# POWER_HALL.net
KiCad netlist of a schematic drawn in Altium Designer
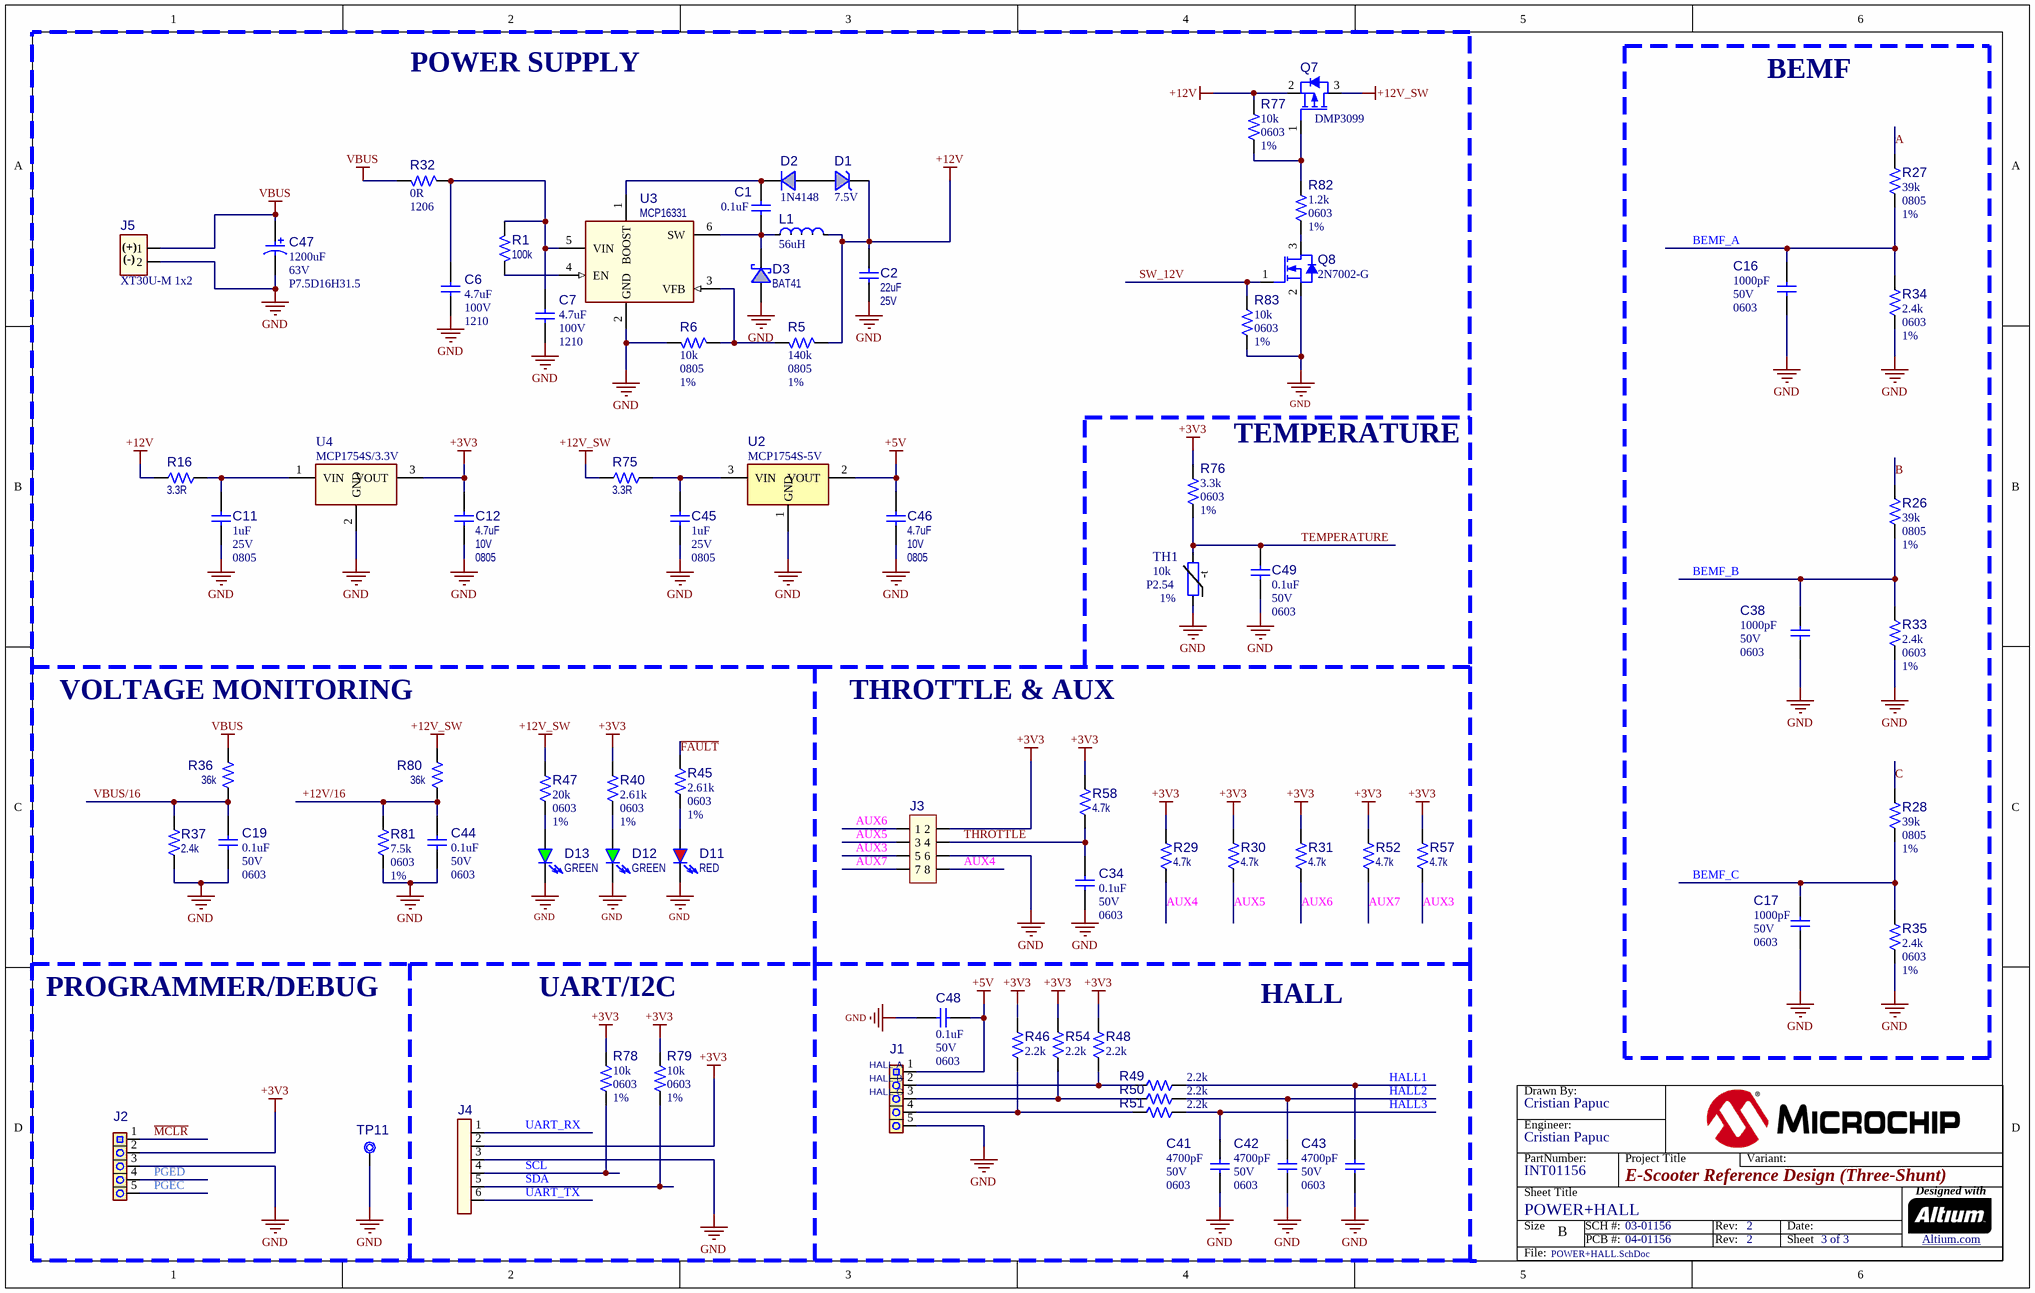
[diagram p0: POWER+HALL.SchDoc]

(export (version "E")
  (design (tool "Eeschema 10.0.6"))
  (components
    (comp (ref "C1")
      (value "0.1uF")
      (footprint "CAP_C_0603")
      (description "Capacitor")
      (fields
        (field (name "VOLTAGE") "50V")
        (field (name "TOLERANCE") "10%")
        (field (name "OWNER") "Sam Charles")
      )
      (libsource (lib "MCHP-CDB") (part "Capacitor NP"))
    )
    (comp (ref "C2")
      (value "22uF")
      (footprint "CAP_C_1206")
      (description "Capacitor")
      (fields
        (field (name "VOLTAGE") "25V")
        (field (name "TOLERANCE") "10%")
        (field (name "Comment") "Capacitor NP")
        (field (name "OWNER") "Jose Garcia")
      )
      (libsource (lib "") (part "Capacitor NP_1"))
    )
    (comp (ref "C6")
      (value "4.7uF")
      (footprint "CAP_C_1210")
      (description "Capacitor")
      (fields
        (field (name "VOLTAGE") "100V")
        (field (name "PACKAGE") "1210")
        (field (name "TOLERANCE") "10%")
        (field (name "Comment") "Capacitor NP")
        (field (name "OWNER") "Cristian Papuc")
      )
      (libsource (lib "MCHP-CDB") (part "Capacitor NP"))
    )
    (comp (ref "C7")
      (value "4.7uF")
      (footprint "CAP_C_1210")
      (description "Capacitor")
      (fields
        (field (name "VOLTAGE") "100V")
        (field (name "PACKAGE") "1210")
        (field (name "TOLERANCE") "10%")
        (field (name "Comment") "Capacitor NP")
        (field (name "OWNER") "Cristian Papuc")
      )
      (libsource (lib "MCHP-CDB") (part "Capacitor NP"))
    )
    (comp (ref "C11")
      (value "1uF")
      (footprint "CAP_C_0805")
      (description "Capacitor")
      (fields
        (field (name "VOLTAGE") "25V")
        (field (name "PACKAGE") "0805")
        (field (name "TOLERANCE") "10%")
        (field (name "Comment") "Capacitor NP")
        (field (name "OWNER") "Tad Ahlvers")
      )
      (libsource (lib "MCHP-CDB") (part "Capacitor NP"))
    )
    (comp (ref "C12")
      (value "4.7uF")
      (footprint "CAP_C_0805")
      (description "Capacitor")
      (fields
        (field (name "VOLTAGE") "10V")
        (field (name "PACKAGE") "0805")
        (field (name "TOLERANCE") "20%")
        (field (name "Comment") "Capacitor NP")
        (field (name "OWNER") "Mark Loper")
      )
      (libsource (lib "") (part "Capacitor NP_1"))
    )
    (comp (ref "C16")
      (value "1000pF")
      (footprint "CAP_C_0603")
      (description "Capacitor")
      (fields
        (field (name "VOLTAGE") "50V")
        (field (name "PACKAGE") "0603")
        (field (name "TOLERANCE") "10%")
        (field (name "Comment") "Capacitor NP")
      )
      (libsource (lib "") (part "Capacitor NP_1"))
    )
    (comp (ref "C17")
      (value "1000pF")
      (footprint "CAP_C_0603")
      (description "Capacitor")
      (fields
        (field (name "VOLTAGE") "50V")
        (field (name "PACKAGE") "0603")
        (field (name "TOLERANCE") "10%")
        (field (name "Comment") "Capacitor NP")
      )
      (libsource (lib "") (part "Capacitor NP_1"))
    )
    (comp (ref "C19")
      (value "0.1uF")
      (footprint "CAP_C_0603")
      (description "Capacitor")
      (fields
        (field (name "VOLTAGE") "50V")
        (field (name "PACKAGE") "0603")
        (field (name "TOLERANCE") "10%")
        (field (name "Comment") "Capacitor NP")
        (field (name "OWNER") "Sam Charles")
      )
      (libsource (lib "MCHP-CDB") (part "Capacitor NP"))
    )
    (comp (ref "C34")
      (value "0.1uF")
      (footprint "CAP_C_0603")
      (description "Capacitor")
      (fields
        (field (name "VOLTAGE") "50V")
        (field (name "PACKAGE") "0603")
        (field (name "TOLERANCE") "10%")
        (field (name "Comment") "Capacitor NP")
        (field (name "OWNER") "Sam Charles")
      )
      (libsource (lib "MCHP-CDB") (part "Capacitor NP"))
    )
    (comp (ref "C38")
      (value "1000pF")
      (footprint "CAP_C_0603")
      (description "Capacitor")
      (fields
        (field (name "VOLTAGE") "50V")
        (field (name "PACKAGE") "0603")
        (field (name "TOLERANCE") "10%")
        (field (name "Comment") "Capacitor NP")
      )
      (libsource (lib "") (part "Capacitor NP_1"))
    )
    (comp (ref "C41")
      (value "4700pF")
      (footprint "CAP_C_0603")
      (fields
        (field (name "VOLTAGE") "50V")
        (field (name "PACKAGE") "0603")
        (field (name "TOLERANCE") "10%")
        (field (name "Comment") "Capacitor NP")
        (field (name "OWNER") "Miahi T(M91442)")
      )
      (libsource (lib "MCHP-CDB") (part "Capacitor NP"))
    )
    (comp (ref "C42")
      (value "4700pF")
      (footprint "CAP_C_0603")
      (fields
        (field (name "VOLTAGE") "50V")
        (field (name "PACKAGE") "0603")
        (field (name "TOLERANCE") "10%")
        (field (name "Comment") "Capacitor NP")
        (field (name "OWNER") "Miahi T(M91442)")
      )
      (libsource (lib "MCHP-CDB") (part "Capacitor NP"))
    )
    (comp (ref "C43")
      (value "4700pF")
      (footprint "CAP_C_0603")
      (fields
        (field (name "VOLTAGE") "50V")
        (field (name "PACKAGE") "0603")
        (field (name "TOLERANCE") "10%")
        (field (name "Comment") "Capacitor NP")
        (field (name "OWNER") "Miahi T(M91442)")
      )
      (libsource (lib "MCHP-CDB") (part "Capacitor NP"))
    )
    (comp (ref "C44")
      (value "0.1uF")
      (footprint "CAP_C_0603")
      (description "Capacitor")
      (fields
        (field (name "VOLTAGE") "50V")
        (field (name "PACKAGE") "0603")
        (field (name "TOLERANCE") "10%")
        (field (name "Comment") "Capacitor NP")
        (field (name "OWNER") "Sam Charles")
      )
      (libsource (lib "MCHP-CDB") (part "Capacitor NP"))
    )
    (comp (ref "C45")
      (value "1uF")
      (footprint "CAP_C_0805")
      (description "Capacitor")
      (fields
        (field (name "VOLTAGE") "25V")
        (field (name "PACKAGE") "0805")
        (field (name "TOLERANCE") "10%")
        (field (name "Comment") "Capacitor NP")
        (field (name "OWNER") "Tad Ahlvers")
      )
      (libsource (lib "MCHP-CDB") (part "Capacitor NP"))
    )
    (comp (ref "C46")
      (value "4.7uF")
      (footprint "CAP_C_0805")
      (description "Capacitor")
      (fields
        (field (name "VOLTAGE") "10V")
        (field (name "PACKAGE") "0805")
        (field (name "TOLERANCE") "20%")
        (field (name "Comment") "Capacitor NP")
        (field (name "OWNER") "Mark Loper")
      )
      (libsource (lib "") (part "Capacitor NP_1"))
    )
    (comp (ref "C47")
      (value "1200uF")
      (footprint "CAP_RAD_P7.5D16H31.5")
      (description "Capacitor")
      (fields
        (field (name "VOLTAGE") "63V")
        (field (name "PACKAGE") "P7.5D16H31.5")
        (field (name "TOLERANCE") "20%")
        (field (name "Comment") "Capacitor POL")
        (field (name "OWNER") "Cristina Salanti")
      )
      (libsource (lib "MCHP-CDB") (part "Capacitor POL"))
    )
    (comp (ref "C48")
      (value "0.1uF")
      (footprint "CAP_C_0603")
      (description "Capacitor")
      (fields
        (field (name "VOLTAGE") "50V")
        (field (name "PACKAGE") "0603")
        (field (name "TOLERANCE") "10%")
        (field (name "Comment") "Capacitor NP")
        (field (name "OWNER") "Sam Charles")
      )
      (libsource (lib "MCHP-CDB") (part "Capacitor NP"))
    )
    (comp (ref "C49")
      (value "0.1uF")
      (footprint "CAP_C_0603")
      (description "Capacitor")
      (fields
        (field (name "VOLTAGE") "50V")
        (field (name "PACKAGE") "0603")
        (field (name "TOLERANCE") "10%")
        (field (name "Comment") "Capacitor NP")
        (field (name "OWNER") "Sam Charles")
      )
      (libsource (lib "MCHP-CDB") (part "Capacitor NP"))
    )
    (comp (ref "D1")
      (value "7.5V")
      (footprint "SOD-123")
      (fields
        (field (name "POWER") "500mW")
        (field (name "Comment") "Diode Zener")
        (field (name "OWNER") "Cristian Papuc")
      )
      (libsource (lib "MCHP-CDB") (part "Diode Zener"))
    )
    (comp (ref "D2")
      (value "1N4148")
      (footprint "SOD-323")
      (fields (field (name "POWER") "200mW") (field (name "Comment") "Diode Single"))
      (libsource (lib "MCHP-CDB") (part "Diode Single"))
    )
    (comp (ref "D3")
      (value "BAT41")
      (footprint "SOD-123")
      (fields (field (name "Comment") "Diode Schottky"))
      (libsource (lib "MCHP-CDB") (part "Diode Schottky"))
    )
    (comp (ref "D11")
      (value "RED")
      (footprint "LED_0603_RED")
      (description "LED")
      (fields
        (field (name "POWER") "100mW")
        (field (name "Comment") "LED_red")
        (field (name "OWNER") "Tad Ahlvers")
      )
      (libsource (lib "MCHP-CDB") (part "LED_red"))
    )
    (comp (ref "D12")
      (value "GREEN")
      (footprint "LED_0603_GREEN")
      (description "LED")
      (fields
        (field (name "POWER") "75mW")
        (field (name "Comment") "LED_green")
        (field (name "OWNER") "Tad Ahlvers")
      )
      (libsource (lib "MCHP-CDB") (part "LED_green"))
    )
    (comp (ref "D13")
      (value "GREEN")
      (footprint "LED_0603_GREEN")
      (description "LED")
      (fields
        (field (name "POWER") "75mW")
        (field (name "Comment") "LED_green")
        (field (name "OWNER") "Tad Ahlvers")
      )
      (libsource (lib "MCHP-CDB") (part "LED_green"))
    )
    (comp (ref "J1")
      (value "Header 1x5")
      (footprint "HDR_M_2.54_1x5")
      (libsource (lib "MCHP-CDB") (part "Header 1x5"))
    )
    (comp (ref "J2")
      (value "Header 1x5")
      (footprint "HDR_M_2.54_1x5")
      (libsource (lib "MCHP-CDB") (part "Header 1x5"))
    )
    (comp (ref "J3")
      (value "Header 2x4")
      (footprint "HDR_M_2.54_2x4")
      (fields (field (name "OWNER") "Randolph Sobrepena"))
      (libsource (lib "MCHP-CDB") (part "Header 2x4"))
    )
    (comp (ref "J4")
      (value "Header 1x6")
      (footprint "HDR_M_2.54_1x6")
      (fields (field (name "OWNER") "Octavian Stroe"))
      (libsource (lib "MCHP-CDB") (part "Header 1x6"))
    )
    (comp (ref "J5")
      (value "XT30U-M 1x2")
      (footprint "CON TERMINAL XT30U-M 5mm 1x2 Male 30A TH V")
      (fields
        (field (name "VOLTAGE") "500V")
        (field (name "Comment") "CON 1x2 POLARIZED")
        (field (name "OWNER") "Octavian Stroe")
      )
      (libsource (lib "MCHP-CDB") (part "CON 1x2 POLARIZED"))
    )
    (comp (ref "L1")
      (value "56uH")
      (footprint "IND_WE_WE-PD_L7.3W7.3H4.5")
      (description "Inductor")
      (fields (field (name "OWNER") "Bogdan P (M91398)"))
      (libsource (lib "MCHP-CDB") (part "Inductor"))
    )
    (comp (ref "Q7")
      (value "DMP3099")
      (footprint "SOT-23-3")
      (description "Transistor MOS")
      (fields
        (field (name "POWER") "1.08W")
        (field (name "Comment") "Transistor MOS-P GSD")
        (field (name "OWNER") "Alexandru Chiser - M19201")
      )
      (libsource (lib "MCHP-CDB") (part "Transistor MOS-P GSD"))
    )
    (comp (ref "Q8")
      (value "2N7002-G")
      (footprint "SOT-23-3")
      (description "Transistor MOS")
      (fields (field (name "Comment") "Transistor MOS-N GSD") (field (name "OWNER") "Mark Loper"))
      (libsource (lib "MCHP-CDB") (part "Transistor MOS-N GSD"))
    )
    (comp (ref "R1")
      (value "100k")
      (footprint "RES_C_0603")
      (description "Resistor")
      (fields
        (field (name "TOLERANCE") "1%")
        (field (name "VOLTAGE") "75V")
        (field (name "OWNER") "Tad Ahlvers")
      )
      (libsource (lib "MCHP-CDB") (part "Resistor"))
    )
    (comp (ref "R5")
      (value "140k")
      (footprint "RES_C_0805")
      (description "Resistor")
      (fields
        (field (name "PACKAGE") "0805")
        (field (name "TOLERANCE") "1%")
        (field (name "VOLTAGE") "150V")
        (field (name "POWER") "1/8W")
        (field (name "OWNER") "Bogdan Popescu")
      )
      (libsource (lib "MCHP-CDB") (part "Resistor"))
    )
    (comp (ref "R6")
      (value "10k")
      (footprint "RES_C_0805")
      (description "Resistor")
      (fields
        (field (name "PACKAGE") "0805")
        (field (name "TOLERANCE") "1%")
        (field (name "VOLTAGE") "150V")
        (field (name "POWER") "1/8W")
      )
      (libsource (lib "MCHP-CDB") (part "Resistor"))
    )
    (comp (ref "R16")
      (value "3.3R")
      (footprint "RES_C_0805")
      (description "Resistor")
      (fields
        (field (name "TOLERANCE") "1%")
        (field (name "POWER") "1/8W")
        (field (name "OWNER") "Gabor Bihari")
      )
      (libsource (lib "MCHP-CDB") (part "Resistor"))
    )
    (comp (ref "R26")
      (value "39k")
      (footprint "RES_C_0805")
      (description "Resistor")
      (fields
        (field (name "PACKAGE") "0805")
        (field (name "TOLERANCE") "1%")
        (field (name "VOLTAGE") "150V")
        (field (name "POWER") "1/8W")
        (field (name "OWNER") "Octavian Stroe")
      )
      (libsource (lib "MCHP-CDB") (part "Resistor"))
    )
    (comp (ref "R27")
      (value "39k")
      (footprint "RES_C_0805")
      (description "Resistor")
      (fields
        (field (name "PACKAGE") "0805")
        (field (name "TOLERANCE") "1%")
        (field (name "VOLTAGE") "150V")
        (field (name "POWER") "1/8W")
        (field (name "OWNER") "Octavian Stroe")
      )
      (libsource (lib "MCHP-CDB") (part "Resistor"))
    )
    (comp (ref "R28")
      (value "39k")
      (footprint "RES_C_0805")
      (description "Resistor")
      (fields
        (field (name "PACKAGE") "0805")
        (field (name "TOLERANCE") "1%")
        (field (name "VOLTAGE") "150V")
        (field (name "POWER") "1/8W")
        (field (name "OWNER") "Octavian Stroe")
      )
      (libsource (lib "MCHP-CDB") (part "Resistor"))
    )
    (comp (ref "R29")
      (value "4.7k")
      (footprint "RES_C_0603")
      (description "Resistor")
      (fields (field (name "TOLERANCE") "1%") (field (name "VOLTAGE") "50V"))
      (libsource (lib "MCHP-CDB") (part "Resistor"))
    )
    (comp (ref "R30")
      (value "4.7k")
      (footprint "RES_C_0603")
      (description "Resistor")
      (fields (field (name "TOLERANCE") "1%") (field (name "VOLTAGE") "50V"))
      (libsource (lib "MCHP-CDB") (part "Resistor"))
    )
    (comp (ref "R31")
      (value "4.7k")
      (footprint "RES_C_0603")
      (description "Resistor")
      (fields (field (name "TOLERANCE") "1%") (field (name "VOLTAGE") "50V"))
      (libsource (lib "MCHP-CDB") (part "Resistor"))
    )
    (comp (ref "R32")
      (value "0R")
      (footprint "RES_C_1206")
      (description "Resistor")
      (fields (field (name "PACKAGE") "1206"))
      (libsource (lib "MCHP-CDB") (part "Resistor"))
    )
    (comp (ref "R33")
      (value "2.4k")
      (footprint "RES_C_0603")
      (description "Resistor")
      (fields
        (field (name "PACKAGE") "0603")
        (field (name "TOLERANCE") "1%")
        (field (name "VOLTAGE") "75V")
        (field (name "POWER") "1/10W")
        (field (name "OWNER") "Henry de Villiers")
      )
      (libsource (lib "MCHP-CDB") (part "Resistor"))
    )
    (comp (ref "R34")
      (value "2.4k")
      (footprint "RES_C_0603")
      (description "Resistor")
      (fields
        (field (name "PACKAGE") "0603")
        (field (name "TOLERANCE") "1%")
        (field (name "VOLTAGE") "75V")
        (field (name "POWER") "1/10W")
        (field (name "OWNER") "Henry de Villiers")
      )
      (libsource (lib "MCHP-CDB") (part "Resistor"))
    )
    (comp (ref "R35")
      (value "2.4k")
      (footprint "RES_C_0603")
      (description "Resistor")
      (fields
        (field (name "PACKAGE") "0603")
        (field (name "TOLERANCE") "1%")
        (field (name "VOLTAGE") "75V")
        (field (name "POWER") "1/10W")
        (field (name "OWNER") "Henry de Villiers")
      )
      (libsource (lib "MCHP-CDB") (part "Resistor"))
    )
    (comp (ref "R36")
      (value "36k")
      (footprint "RES_C_0805")
      (description "Resistor")
      (fields (field (name "TOLERANCE") "1%") (field (name "VOLTAGE") "150V"))
      (libsource (lib "MCHP-CDB") (part "Resistor"))
    )
    (comp (ref "R37")
      (value "2.4k")
      (footprint "RES_C_0603")
      (description "Resistor")
      (fields
        (field (name "TOLERANCE") "1%")
        (field (name "POWER") "1/10W")
        (field (name "OWNER") "Henry de Villiers")
      )
      (libsource (lib "MCHP-CDB") (part "Resistor"))
    )
    (comp (ref "R40")
      (value "2.61k")
      (footprint "RES_C_0603")
      (description "Resistor")
      (fields
        (field (name "PACKAGE") "0603")
        (field (name "TOLERANCE") "1%")
        (field (name "VOLTAGE") "50V")
        (field (name "POWER") "1/16W")
        (field (name "OWNER") "Mihai T(M91442)")
      )
      (libsource (lib "MCHP-CDB") (part "Resistor"))
    )
    (comp (ref "R45")
      (value "2.61k")
      (footprint "RES_C_0603")
      (description "Resistor")
      (fields
        (field (name "PACKAGE") "0603")
        (field (name "TOLERANCE") "1%")
        (field (name "VOLTAGE") "50V")
        (field (name "POWER") "1/16W")
        (field (name "OWNER") "Mihai T(M91442)")
      )
      (libsource (lib "MCHP-CDB") (part "Resistor"))
    )
    (comp (ref "R46")
      (value "2.2k")
      (footprint "RES_C_0603")
      (description "Resistor")
      (fields
        (field (name "TOLERANCE") "1%")
        (field (name "VOLTAGE") "75V")
        (field (name "OWNER") "Bogdan P (M91398)")
      )
      (libsource (lib "MCHP-CDB") (part "Resistor"))
    )
    (comp (ref "R47")
      (value "20k")
      (footprint "RES_C_0603")
      (description "Resistor")
      (fields
        (field (name "PACKAGE") "0603")
        (field (name "TOLERANCE") "1%")
        (field (name "VOLTAGE") "50V")
        (field (name "POWER") "1/10W")
      )
      (libsource (lib "MCHP-CDB") (part "Resistor"))
    )
    (comp (ref "R48")
      (value "2.2k")
      (footprint "RES_C_0603")
      (description "Resistor")
      (fields
        (field (name "TOLERANCE") "1%")
        (field (name "VOLTAGE") "75V")
        (field (name "OWNER") "Bogdan P (M91398)")
      )
      (libsource (lib "MCHP-CDB") (part "Resistor"))
    )
    (comp (ref "R49")
      (value "2.2k")
      (footprint "RES_C_0603")
      (description "Resistor")
      (fields
        (field (name "POWER") "1/10W")
        (field (name "TOLERANCE") "1%")
        (field (name "OWNER") "Bogdan P (M91398)")
      )
      (libsource (lib "MCHP-CDB") (part "Resistor"))
    )
    (comp (ref "R50")
      (value "2.2k")
      (footprint "RES_C_0603")
      (description "Resistor")
      (fields
        (field (name "POWER") "1/10W")
        (field (name "TOLERANCE") "1%")
        (field (name "OWNER") "Bogdan P (M91398)")
      )
      (libsource (lib "MCHP-CDB") (part "Resistor"))
    )
    (comp (ref "R51")
      (value "2.2k")
      (footprint "RES_C_0603")
      (description "Resistor")
      (fields
        (field (name "POWER") "1/10W")
        (field (name "TOLERANCE") "1%")
        (field (name "OWNER") "Bogdan P (M91398)")
      )
      (libsource (lib "MCHP-CDB") (part "Resistor"))
    )
    (comp (ref "R52")
      (value "4.7k")
      (footprint "RES_C_0603")
      (description "Resistor")
      (fields (field (name "TOLERANCE") "1%") (field (name "VOLTAGE") "50V"))
      (libsource (lib "MCHP-CDB") (part "Resistor"))
    )
    (comp (ref "R54")
      (value "2.2k")
      (footprint "RES_C_0603")
      (description "Resistor")
      (fields
        (field (name "TOLERANCE") "1%")
        (field (name "VOLTAGE") "75V")
        (field (name "OWNER") "Bogdan P (M91398)")
      )
      (libsource (lib "MCHP-CDB") (part "Resistor"))
    )
    (comp (ref "R57")
      (value "4.7k")
      (footprint "RES_C_0603")
      (description "Resistor")
      (fields (field (name "TOLERANCE") "1%") (field (name "VOLTAGE") "50V"))
      (libsource (lib "MCHP-CDB") (part "Resistor"))
    )
    (comp (ref "R58")
      (value "4.7k")
      (footprint "RES_C_0603")
      (description "Resistor")
      (fields (field (name "TOLERANCE") "1%") (field (name "VOLTAGE") "50V"))
      (libsource (lib "MCHP-CDB") (part "Resistor"))
    )
    (comp (ref "R75")
      (value "3.3R")
      (footprint "RES_C_0805")
      (description "Resistor")
      (fields
        (field (name "TOLERANCE") "1%")
        (field (name "POWER") "1/8W")
        (field (name "OWNER") "Gabor Bihari")
      )
      (libsource (lib "MCHP-CDB") (part "Resistor"))
    )
    (comp (ref "R76")
      (value "3.3k")
      (footprint "RES_C_0603")
      (description "Resistor")
      (fields
        (field (name "PACKAGE") "0603")
        (field (name "TOLERANCE") "1%")
        (field (name "POWER") "1/10W")
        (field (name "VOLTAGE") "75V")
      )
      (libsource (lib "MCHP-CDB") (part "Resistor"))
    )
    (comp (ref "R77")
      (value "10k")
      (footprint "RES_C_0603")
      (description "Resistor")
      (fields (field (name "PACKAGE") "0603") (field (name "TOLERANCE") "1%") (field (name "POWER") "1/10W"))
      (libsource (lib "MCHP-CDB") (part "Resistor"))
    )
    (comp (ref "R78")
      (value "10k")
      (footprint "RES_C_0603")
      (description "Resistor")
      (fields (field (name "PACKAGE") "0603") (field (name "TOLERANCE") "1%") (field (name "POWER") "1/10W"))
      (libsource (lib "MCHP-CDB") (part "Resistor"))
    )
    (comp (ref "R79")
      (value "10k")
      (footprint "RES_C_0603")
      (description "Resistor")
      (fields (field (name "PACKAGE") "0603") (field (name "TOLERANCE") "1%") (field (name "POWER") "1/10W"))
      (libsource (lib "MCHP-CDB") (part "Resistor"))
    )
    (comp (ref "R80")
      (value "36k")
      (footprint "RES_C_0805")
      (description "Resistor")
      (fields (field (name "TOLERANCE") "1%") (field (name "VOLTAGE") "150V"))
      (libsource (lib "MCHP-CDB") (part "Resistor"))
    )
    (comp (ref "R81")
      (value "7.5k")
      (footprint "RES_C_0603")
      (description "Resistor")
      (fields
        (field (name "PACKAGE") "0603")
        (field (name "TOLERANCE") "1%")
        (field (name "VOLTAGE") "75V")
        (field (name "POWER") "1/10W")
      )
      (libsource (lib "MCHP-CDB") (part "Resistor"))
    )
    (comp (ref "R82")
      (value "1.2k")
      (footprint "RES_C_0603")
      (description "Resistor")
      (fields
        (field (name "PACKAGE") "0603")
        (field (name "TOLERANCE") "1%")
        (field (name "VOLTAGE") "50V")
        (field (name "POWER") "1/10W")
        (field (name "OWNER") "Aaron VanDuerm")
      )
      (libsource (lib "MCHP-CDB") (part "Resistor"))
    )
    (comp (ref "R83")
      (value "10k")
      (footprint "RES_C_0603")
      (description "Resistor")
      (fields (field (name "PACKAGE") "0603") (field (name "TOLERANCE") "1%") (field (name "POWER") "1/10W"))
      (libsource (lib "MCHP-CDB") (part "Resistor"))
    )
    (comp (ref "TH1")
      (value "10k")
      (footprint "Thermistor_Wired_P1.5")
      (fields
        (field (name "PACKAGE") "P2.54")
        (field (name "TOLERANCE") "1%")
        (field (name "POWER") "60mW")
        (field (name "Comment") "Thermistor NTC")
        (field (name "OWNER") "Octavian Stroe")
      )
      (libsource (lib "MCHP-CDB") (part "Thermistor NTC"))
    )
    (comp (ref "TP11")
      (value "Test Point No BOM")
      (footprint "TP_3.4x5_SMD_NOBOM")
      (description "Test Point")
      (fields (field (name "OWNER") "Gabor Bihari"))
      (libsource (lib "MCHP-CDB") (part "Test Point No BOM"))
    )
    (comp (ref "U2")
      (value "MCP1754S-5V")
      (footprint "SOT-23A-3")
      (description "LDO")
      (fields (field (name "Comment") "MCP1754ST-5002ECB SOT-23A-3") (field (name "OWNER") "Octavian Stroe"))
      (libsource (lib "MCHP-CDB") (part "MCP1754ST-5002ECB SOT-23A-3"))
    )
    (comp (ref "U3")
      (value "MCP16331")
      (footprint "SOT-23-6")
      (description "DC-DC Convertor")
      (fields (field (name "Comment") "MCP16331 SOT-23-6") (field (name "OWNER") "Bogdan Popescu"))
      (libsource (lib "MCHP-CDB") (part "MCP16331 SOT-23-6"))
    )
    (comp (ref "U4")
      (value "MCP1754S/3.3V")
      (footprint "SOT-223-3")
      (description "LDO")
      (fields (field (name "Comment") "MCP1754S SOT-89-3_SOT-223-3") (field (name "OWNER") "Tad Ahlvers"))
      (libsource (lib "MCHP-CDB") (part "MCP1754S SOT-89-3_SOT-223-3"))
    )
  )
  (nets
    (net (code "1") (name "+3V3") (class "Default")
      (node (ref "C12") (pin "2") (pinfunction "2_2") (pintype "passive"))
      (node (ref "J2") (pin "2") (pinfunction "P2_2") (pintype "passive"))
      (node (ref "J3") (pin "2") (pinfunction "2_2") (pintype "passive"))
      (node (ref "J4") (pin "2") (pinfunction "2_2") (pintype "passive"))
      (node (ref "R29") (pin "2") (pinfunction "2_2") (pintype "passive"))
      (node (ref "R30") (pin "2") (pinfunction "2_2") (pintype "passive"))
      (node (ref "R31") (pin "2") (pinfunction "2_2") (pintype "passive"))
      (node (ref "R40") (pin "2") (pinfunction "2_2") (pintype "passive"))
      (node (ref "R46") (pin "2") (pinfunction "2_2") (pintype "passive"))
      (node (ref "R48") (pin "2") (pinfunction "2_2") (pintype "passive"))
      (node (ref "R52") (pin "2") (pinfunction "2_2") (pintype "passive"))
      (node (ref "R54") (pin "2") (pinfunction "2_2") (pintype "passive"))
      (node (ref "R57") (pin "2") (pinfunction "2_2") (pintype "passive"))
      (node (ref "R58") (pin "2") (pinfunction "2_2") (pintype "passive"))
      (node (ref "R76") (pin "2") (pinfunction "2_2") (pintype "passive"))
      (node (ref "R78") (pin "2") (pinfunction "2_2") (pintype "passive"))
      (node (ref "R79") (pin "2") (pinfunction "2_2") (pintype "passive"))
      (node (ref "U4") (pin "3") (pinfunction "VOUT_3") (pintype "passive"))
    )
    (net (code "2") (name "+5V") (class "Default")
      (node (ref "C46") (pin "2") (pinfunction "2_2") (pintype "passive"))
      (node (ref "C48") (pin "1") (pinfunction "1_1") (pintype "passive"))
      (node (ref "J1") (pin "1") (pinfunction "P1_1") (pintype "passive"))
      (node (ref "U2") (pin "2") (pinfunction "VOUT_2") (pintype "power_in"))
    )
    (net (code "3") (name "+12V") (class "Default")
      (node (ref "C2") (pin "1") (pinfunction "1_1") (pintype "passive"))
      (node (ref "D1") (pin "2") (pinfunction "K_2") (pintype "passive"))
      (node (ref "L1") (pin "1") (pinfunction "S_1") (pintype "passive"))
      (node (ref "Q7") (pin "2") (pinfunction "S_2") (pintype "passive"))
      (node (ref "R16") (pin "1") (pinfunction "1_1") (pintype "passive"))
      (node (ref "R5") (pin "1") (pinfunction "1_1") (pintype "passive"))
      (node (ref "R77") (pin "2") (pinfunction "2_2") (pintype "passive"))
    )
    (net (code "4") (name "+12V_SW") (class "Default")
      (node (ref "Q7") (pin "3") (pinfunction "D_3") (pintype "passive"))
      (node (ref "R47") (pin "2") (pinfunction "2_2") (pintype "passive"))
      (node (ref "R75") (pin "1") (pinfunction "1_1") (pintype "passive"))
      (node (ref "R80") (pin "2") (pinfunction "2_2") (pintype "passive"))
    )
    (net (code "5") (name "/+12V{slash}16") (class "Default")
      (node (ref "C44") (pin "2") (pinfunction "2_2") (pintype "passive"))
      (node (ref "R80") (pin "1") (pinfunction "1_1") (pintype "passive"))
      (node (ref "R81") (pin "2") (pinfunction "2_2") (pintype "passive"))
    )
    (net (code "6") (name "/A") (class "Default")
      (node (ref "R27") (pin "2") (pinfunction "2_2") (pintype "passive"))
    )
    (net (code "7") (name "/AUX3") (class "Default")
      (node (ref "J3") (pin "5") (pinfunction "5_5") (pintype "passive"))
      (node (ref "R57") (pin "1") (pinfunction "1_1") (pintype "passive"))
    )
    (net (code "8") (name "/AUX4") (class "Default")
      (node (ref "J3") (pin "8") (pinfunction "8_8") (pintype "passive"))
      (node (ref "R29") (pin "1") (pinfunction "1_1") (pintype "passive"))
    )
    (net (code "9") (name "/AUX5") (class "Default")
      (node (ref "J3") (pin "3") (pinfunction "3_3") (pintype "passive"))
      (node (ref "R30") (pin "1") (pinfunction "1_1") (pintype "passive"))
    )
    (net (code "10") (name "/AUX6") (class "Default")
      (node (ref "J3") (pin "1") (pinfunction "1_1") (pintype "passive"))
      (node (ref "R31") (pin "1") (pinfunction "1_1") (pintype "passive"))
    )
    (net (code "11") (name "/AUX7") (class "Default")
      (node (ref "J3") (pin "7") (pinfunction "7_7") (pintype "passive"))
      (node (ref "R52") (pin "1") (pinfunction "1_1") (pintype "passive"))
    )
    (net (code "12") (name "/B") (class "Default")
      (node (ref "R26") (pin "2") (pinfunction "2_2") (pintype "passive"))
    )
    (net (code "13") (name "/BEMF_A") (class "Default")
      (node (ref "C16") (pin "2") (pinfunction "2_2") (pintype "passive"))
      (node (ref "R27") (pin "1") (pinfunction "1_1") (pintype "passive"))
      (node (ref "R34") (pin "2") (pinfunction "2_2") (pintype "passive"))
    )
    (net (code "14") (name "/BEMF_B") (class "Default")
      (node (ref "C38") (pin "2") (pinfunction "2_2") (pintype "passive"))
      (node (ref "R26") (pin "1") (pinfunction "1_1") (pintype "passive"))
      (node (ref "R33") (pin "2") (pinfunction "2_2") (pintype "passive"))
    )
    (net (code "15") (name "/BEMF_C") (class "Default")
      (node (ref "C17") (pin "2") (pinfunction "2_2") (pintype "passive"))
      (node (ref "R28") (pin "1") (pinfunction "1_1") (pintype "passive"))
      (node (ref "R35") (pin "2") (pinfunction "2_2") (pintype "passive"))
    )
    (net (code "16") (name "/C") (class "Default")
      (node (ref "R28") (pin "2") (pinfunction "2_2") (pintype "passive"))
    )
    (net (code "17") (name "/FAULT") (class "Default")
      (node (ref "R45") (pin "2") (pinfunction "2_2") (pintype "passive"))
    )
    (net (code "18") (name "/HALL1") (class "Default")
      (node (ref "C43") (pin "2") (pinfunction "2_2") (pintype "passive"))
      (node (ref "R49") (pin "2") (pinfunction "2_2") (pintype "passive"))
    )
    (net (code "19") (name "/HALL2") (class "Default")
      (node (ref "C42") (pin "2") (pinfunction "2_2") (pintype "passive"))
      (node (ref "R50") (pin "2") (pinfunction "2_2") (pintype "passive"))
    )
    (net (code "20") (name "/HALL3") (class "Default")
      (node (ref "C41") (pin "2") (pinfunction "2_2") (pintype "passive"))
      (node (ref "R51") (pin "2") (pinfunction "2_2") (pintype "passive"))
    )
    (net (code "21") (name "/MCLR") (class "Default")
      (node (ref "J2") (pin "1") (pinfunction "P1_1") (pintype "passive"))
    )
    (net (code "22") (name "/PGEC") (class "Default")
      (node (ref "J2") (pin "5") (pinfunction "P5_5") (pintype "passive"))
    )
    (net (code "23") (name "/PGED") (class "Default")
      (node (ref "J2") (pin "4") (pinfunction "P4_4") (pintype "passive"))
    )
    (net (code "24") (name "/SCL") (class "Default")
      (node (ref "J4") (pin "4") (pinfunction "4_4") (pintype "passive"))
      (node (ref "R78") (pin "1") (pinfunction "1_1") (pintype "passive"))
    )
    (net (code "25") (name "/SDA") (class "Default")
      (node (ref "J4") (pin "5") (pinfunction "5_5") (pintype "passive"))
      (node (ref "R79") (pin "1") (pinfunction "1_1") (pintype "passive"))
    )
    (net (code "26") (name "/SW_12V") (class "Default")
      (node (ref "Q8") (pin "1") (pinfunction "G_1") (pintype "passive"))
      (node (ref "R83") (pin "2") (pinfunction "2_2") (pintype "passive"))
    )
    (net (code "27") (name "/TEMPERATURE") (class "Default")
      (node (ref "C49") (pin "1") (pinfunction "1_1") (pintype "passive"))
      (node (ref "R76") (pin "1") (pinfunction "1_1") (pintype "passive"))
      (node (ref "TH1") (pin "2") (pinfunction "2_2") (pintype "passive"))
    )
    (net (code "28") (name "/THROTTLE") (class "Default")
      (node (ref "C34") (pin "2") (pinfunction "2_2") (pintype "passive"))
      (node (ref "J3") (pin "4") (pinfunction "4_4") (pintype "passive"))
      (node (ref "R58") (pin "1") (pinfunction "1_1") (pintype "passive"))
    )
    (net (code "29") (name "/UART_RX") (class "Default")
      (node (ref "J4") (pin "1") (pinfunction "1_1") (pintype "passive"))
    )
    (net (code "30") (name "/UART_TX") (class "Default")
      (node (ref "J4") (pin "6") (pinfunction "6_6") (pintype "passive"))
    )
    (net (code "31") (name "/VBUS{slash}16") (class "Default")
      (node (ref "C19") (pin "2") (pinfunction "2_2") (pintype "passive"))
      (node (ref "R36") (pin "1") (pinfunction "1_1") (pintype "passive"))
      (node (ref "R37") (pin "2") (pinfunction "2_2") (pintype "passive"))
    )
    (net (code "32") (name "GND") (class "Default")
      (node (ref "C11") (pin "1") (pinfunction "1_1") (pintype "passive"))
      (node (ref "C12") (pin "1") (pinfunction "1_1") (pintype "passive"))
      (node (ref "C16") (pin "1") (pinfunction "1_1") (pintype "passive"))
      (node (ref "C17") (pin "1") (pinfunction "1_1") (pintype "passive"))
      (node (ref "C19") (pin "1") (pinfunction "1_1") (pintype "passive"))
      (node (ref "C2") (pin "2") (pinfunction "2_2") (pintype "passive"))
      (node (ref "C34") (pin "1") (pinfunction "1_1") (pintype "passive"))
      (node (ref "C38") (pin "1") (pinfunction "1_1") (pintype "passive"))
      (node (ref "C41") (pin "1") (pinfunction "1_1") (pintype "passive"))
      (node (ref "C42") (pin "1") (pinfunction "1_1") (pintype "passive"))
      (node (ref "C43") (pin "1") (pinfunction "1_1") (pintype "passive"))
      (node (ref "C44") (pin "1") (pinfunction "1_1") (pintype "passive"))
      (node (ref "C45") (pin "1") (pinfunction "1_1") (pintype "passive"))
      (node (ref "C46") (pin "1") (pinfunction "1_1") (pintype "passive"))
      (node (ref "C47") (pin "2") (pinfunction "2_2") (pintype "passive"))
      (node (ref "C48") (pin "2") (pinfunction "2_2") (pintype "passive"))
      (node (ref "C49") (pin "2") (pinfunction "2_2") (pintype "passive"))
      (node (ref "C6") (pin "1") (pinfunction "1_1") (pintype "passive"))
      (node (ref "C7") (pin "1") (pinfunction "1_1") (pintype "passive"))
      (node (ref "D11") (pin "2") (pinfunction "K_2") (pintype "passive"))
      (node (ref "D12") (pin "2") (pinfunction "K_2") (pintype "passive"))
      (node (ref "D13") (pin "2") (pinfunction "K_2") (pintype "passive"))
      (node (ref "D3") (pin "1") (pinfunction "A_1") (pintype "passive"))
      (node (ref "J1") (pin "5") (pinfunction "P5_5") (pintype "passive"))
      (node (ref "J2") (pin "3") (pinfunction "P3_3") (pintype "passive"))
      (node (ref "J3") (pin "6") (pinfunction "6_6") (pintype "passive"))
      (node (ref "J4") (pin "3") (pinfunction "3_3") (pintype "passive"))
      (node (ref "J5") (pin "2") (pinfunction "2_2") (pintype "passive"))
      (node (ref "Q8") (pin "2") (pinfunction "S_2") (pintype "passive"))
      (node (ref "R33") (pin "1") (pinfunction "1_1") (pintype "passive"))
      (node (ref "R34") (pin "1") (pinfunction "1_1") (pintype "passive"))
      (node (ref "R35") (pin "1") (pinfunction "1_1") (pintype "passive"))
      (node (ref "R37") (pin "1") (pinfunction "1_1") (pintype "passive"))
      (node (ref "R6") (pin "2") (pinfunction "2_2") (pintype "passive"))
      (node (ref "R81") (pin "1") (pinfunction "1_1") (pintype "passive"))
      (node (ref "R83") (pin "1") (pinfunction "1_1") (pintype "passive"))
      (node (ref "TH1") (pin "1") (pinfunction "1_1") (pintype "passive"))
      (node (ref "TP11") (pin "1") (pinfunction "1_1") (pintype "passive"))
      (node (ref "U2") (pin "1") (pinfunction "GND_1") (pintype "power_in"))
      (node (ref "U3") (pin "2") (pinfunction "GND_2") (pintype "power_in"))
      (node (ref "U4") (pin "2") (pinfunction "GND_2") (pintype "passive"))
    )
    (net (code "33") (name "Net-(D1-A)") (class "Default")
      (node (ref "D1") (pin "1") (pinfunction "A_1") (pintype "passive"))
      (node (ref "D2") (pin "1") (pinfunction "A_1") (pintype "passive"))
    )
    (net (code "34") (name "Net-(D2-K)") (class "Default")
      (node (ref "C1") (pin "2") (pinfunction "2_2") (pintype "passive"))
      (node (ref "D2") (pin "2") (pinfunction "K_2") (pintype "passive"))
      (node (ref "U3") (pin "1") (pinfunction "BOOST_1") (pintype "passive"))
    )
    (net (code "35") (name "Net-(D3-K)") (class "Default")
      (node (ref "C1") (pin "1") (pinfunction "1_1") (pintype "passive"))
      (node (ref "D3") (pin "2") (pinfunction "K_2") (pintype "passive"))
      (node (ref "L1") (pin "2") (pinfunction "F_2") (pintype "passive"))
      (node (ref "U3") (pin "6") (pinfunction "SW_6") (pintype "passive"))
    )
    (net (code "36") (name "Net-(D11-A)") (class "Default")
      (node (ref "D11") (pin "1") (pinfunction "A_1") (pintype "passive"))
      (node (ref "R45") (pin "1") (pinfunction "1_1") (pintype "passive"))
    )
    (net (code "37") (name "Net-(D12-A)") (class "Default")
      (node (ref "D12") (pin "1") (pinfunction "A_1") (pintype "passive"))
      (node (ref "R40") (pin "1") (pinfunction "1_1") (pintype "passive"))
    )
    (net (code "38") (name "Net-(D13-A)") (class "Default")
      (node (ref "D13") (pin "1") (pinfunction "A_1") (pintype "passive"))
      (node (ref "R47") (pin "1") (pinfunction "1_1") (pintype "passive"))
    )
    (net (code "39") (name "Net-(J1-P2)") (class "Default")
      (node (ref "J1") (pin "2") (pinfunction "P2_2") (pintype "passive"))
      (node (ref "R48") (pin "1") (pinfunction "1_1") (pintype "passive"))
      (node (ref "R49") (pin "1") (pinfunction "1_1") (pintype "passive"))
    )
    (net (code "40") (name "Net-(J1-P3)") (class "Default")
      (node (ref "J1") (pin "3") (pinfunction "P3_3") (pintype "passive"))
      (node (ref "R50") (pin "1") (pinfunction "1_1") (pintype "passive"))
      (node (ref "R54") (pin "1") (pinfunction "1_1") (pintype "passive"))
    )
    (net (code "41") (name "Net-(J1-P4)") (class "Default")
      (node (ref "J1") (pin "4") (pinfunction "P4_4") (pintype "passive"))
      (node (ref "R46") (pin "1") (pinfunction "1_1") (pintype "passive"))
      (node (ref "R51") (pin "1") (pinfunction "1_1") (pintype "passive"))
    )
    (net (code "42") (name "Net-(Q7-G)") (class "Default")
      (node (ref "Q7") (pin "1") (pinfunction "G_1") (pintype "passive"))
      (node (ref "R77") (pin "1") (pinfunction "1_1") (pintype "passive"))
      (node (ref "R82") (pin "2") (pinfunction "2_2") (pintype "passive"))
    )
    (net (code "43") (name "Net-(Q8-D)") (class "Default")
      (node (ref "Q8") (pin "3") (pinfunction "D_3") (pintype "passive"))
      (node (ref "R82") (pin "1") (pinfunction "1_1") (pintype "passive"))
    )
    (net (code "44") (name "Net-(U2-VIN)") (class "Default")
      (node (ref "C45") (pin "2") (pinfunction "2_2") (pintype "passive"))
      (node (ref "R75") (pin "2") (pinfunction "2_2") (pintype "passive"))
      (node (ref "U2") (pin "3") (pinfunction "VIN_3") (pintype "power_in"))
    )
    (net (code "45") (name "Net-(U3-EN)") (class "Default")
      (node (ref "R1") (pin "1") (pinfunction "1_1") (pintype "passive"))
      (node (ref "U3") (pin "4") (pinfunction "EN_4") (pintype "input"))
    )
    (net (code "46") (name "Net-(U3-VFB)") (class "Default")
      (node (ref "R5") (pin "2") (pinfunction "2_2") (pintype "passive"))
      (node (ref "R6") (pin "1") (pinfunction "1_1") (pintype "passive"))
      (node (ref "U3") (pin "3") (pinfunction "VFB_3") (pintype "input"))
    )
    (net (code "47") (name "Net-(U3-VIN)") (class "Default")
      (node (ref "C6") (pin "2") (pinfunction "2_2") (pintype "passive"))
      (node (ref "C7") (pin "2") (pinfunction "2_2") (pintype "passive"))
      (node (ref "R1") (pin "2") (pinfunction "2_2") (pintype "passive"))
      (node (ref "R32") (pin "1") (pinfunction "1_1") (pintype "passive"))
      (node (ref "U3") (pin "5") (pinfunction "VIN_5") (pintype "power_in"))
    )
    (net (code "48") (name "Net-(U4-VIN)") (class "Default")
      (node (ref "C11") (pin "2") (pinfunction "2_2") (pintype "passive"))
      (node (ref "R16") (pin "2") (pinfunction "2_2") (pintype "passive"))
      (node (ref "U4") (pin "1") (pinfunction "VIN_1") (pintype "passive"))
    )
    (net (code "49") (name "VBUS") (class "Default")
      (node (ref "C47") (pin "1") (pinfunction "1_1") (pintype "passive"))
      (node (ref "J5") (pin "1") (pinfunction "1_1") (pintype "passive"))
      (node (ref "R32") (pin "2") (pinfunction "2_2") (pintype "passive"))
      (node (ref "R36") (pin "2") (pinfunction "2_2") (pintype "passive"))
    )
  )
)
